# DCSource5V0.net
KiCad netlist of a schematic drawn in Altium Designer
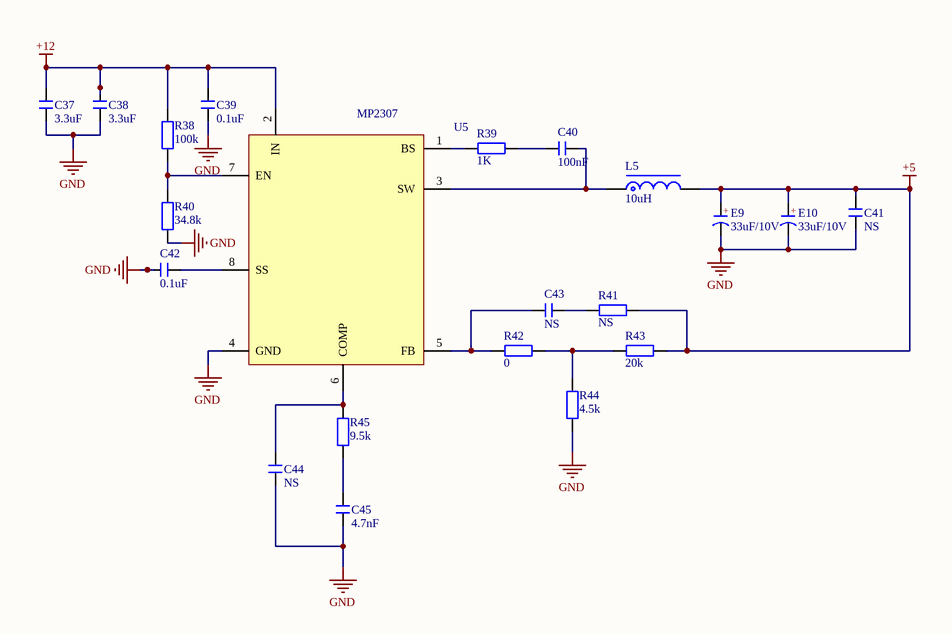
[diagram p0: DCSource5V0.SchDoc]

(export (version "E")
  (design (tool "Eeschema 10.0.6"))
  (components
    (comp (ref "C37")
      (value "3.3uF")
      (footprint "C 0805_L")
      (description "无极性贴片电容")
      (libsource (lib "电容-电阻-电感-电位器") (part "C"))
    )
    (comp (ref "C38")
      (value "3.3uF")
      (footprint "C 0805_L")
      (description "无极性贴片电容")
      (libsource (lib "电容-电阻-电感-电位器") (part "C"))
    )
    (comp (ref "C39")
      (value "0.1uF")
      (footprint "C 0805_L")
      (description "无极性贴片电容")
      (libsource (lib "电容-电阻-电感-电位器") (part "C"))
    )
    (comp (ref "C40")
      (value "100nF")
      (footprint "C 0805_L")
      (description "无极性贴片电容")
      (libsource (lib "电容-电阻-电感-电位器") (part "C"))
    )
    (comp (ref "C41")
      (value "NS")
      (footprint "C 0805_L")
      (description "无极性贴片电容")
      (libsource (lib "电容-电阻-电感-电位器") (part "C"))
    )
    (comp (ref "C42")
      (value "0.1uF")
      (footprint "C 0805_L")
      (description "无极性贴片电容")
      (libsource (lib "电容-电阻-电感-电位器") (part "C"))
    )
    (comp (ref "C43")
      (value "NS")
      (footprint "C 0805_L")
      (description "无极性贴片电容")
      (libsource (lib "电容-电阻-电感-电位器") (part "C"))
    )
    (comp (ref "C44")
      (value "NS")
      (footprint "C 0805_L")
      (description "无极性贴片电容")
      (libsource (lib "电容-电阻-电感-电位器") (part "C"))
    )
    (comp (ref "C45")
      (value "4.7nF")
      (footprint "C 0805_L")
      (description "无极性贴片电容")
      (libsource (lib "电容-电阻-电感-电位器") (part "C"))
    )
    (comp (ref "E9")
      (value "33uF/10V")
      (footprint "CT 5*6 - C")
      (description "贴片固态电容")
      (libsource (lib "电容-电阻-电感-电位器") (part "C-CT"))
    )
    (comp (ref "E10")
      (value "33uF/10V")
      (footprint "CT 5*6 - C")
      (description "贴片固态电容")
      (libsource (lib "电容-电阻-电感-电位器") (part "C-CT"))
    )
    (comp (ref "L5")
      (value "10uH")
      (footprint "CD31")
      (description "贴片功率电感")
      (libsource (lib "电容-电阻-电感-电位器") (part "L-CD"))
    )
    (comp (ref "R38")
      (value "100k")
      (footprint "R 0805_L")
      (description "贴片电阻")
      (libsource (lib "电容-电阻-电感-电位器") (part "R"))
    )
    (comp (ref "R39")
      (value "1K")
      (footprint "R 0805_L")
      (description "贴片电阻")
      (libsource (lib "电容-电阻-电感-电位器") (part "R"))
    )
    (comp (ref "R40")
      (value "34.8k")
      (footprint "R 0805_L")
      (description "贴片电阻")
      (libsource (lib "电容-电阻-电感-电位器") (part "R"))
    )
    (comp (ref "R41")
      (value "NS")
      (footprint "R 0805_L")
      (description "贴片电阻")
      (libsource (lib "电容-电阻-电感-电位器") (part "R"))
    )
    (comp (ref "R42")
      (value "0")
      (footprint "R 0805_L")
      (description "贴片电阻")
      (libsource (lib "电容-电阻-电感-电位器") (part "R"))
    )
    (comp (ref "R43")
      (value "20k")
      (footprint "R 0805_L")
      (description "贴片电阻")
      (libsource (lib "电容-电阻-电感-电位器") (part "R"))
    )
    (comp (ref "R44")
      (value "4.5k")
      (footprint "R 0805_L")
      (description "贴片电阻")
      (libsource (lib "电容-电阻-电感-电位器") (part "R"))
    )
    (comp (ref "R45")
      (value "9.5k")
      (footprint "R 0805_L")
      (description "贴片电阻")
      (libsource (lib "电容-电阻-电感-电位器") (part "R"))
    )
    (comp (ref "U5") (value "MP2307") (footprint "SOP8_M") (libsource (lib "Schlib1") (part "Component_1")))
  )
  (nets
    (net (code "1") (name "+5") (class "Default")
      (node (ref "C41") (pin "2") (pinfunction "2_2") (pintype "passive"))
      (node (ref "E10") (pin "1") (pinfunction "A_1") (pintype "passive"))
      (node (ref "E9") (pin "1") (pinfunction "A_1") (pintype "passive"))
      (node (ref "L5") (pin "2") (pinfunction "2_2") (pintype "passive"))
      (node (ref "R41") (pin "1") (pinfunction "1_1") (pintype "passive"))
      (node (ref "R43") (pin "2") (pinfunction "2_2") (pintype "passive"))
    )
    (net (code "2") (name "+12") (class "Default")
      (node (ref "C37") (pin "2") (pinfunction "2_2") (pintype "passive"))
      (node (ref "C38") (pin "2") (pinfunction "2_2") (pintype "passive"))
      (node (ref "C39") (pin "2") (pinfunction "2_2") (pintype "passive"))
      (node (ref "R38") (pin "2") (pinfunction "2_2") (pintype "passive"))
      (node (ref "U5") (pin "2") (pinfunction "IN_2") (pintype "passive"))
    )
    (net (code "3") (name "GND") (class "Default")
      (node (ref "C37") (pin "1") (pinfunction "1_1") (pintype "passive"))
      (node (ref "C38") (pin "1") (pinfunction "1_1") (pintype "passive"))
      (node (ref "C39") (pin "1") (pinfunction "1_1") (pintype "passive"))
      (node (ref "C41") (pin "1") (pinfunction "1_1") (pintype "passive"))
      (node (ref "C42") (pin "2") (pinfunction "2_2") (pintype "passive"))
      (node (ref "C44") (pin "1") (pinfunction "1_1") (pintype "passive"))
      (node (ref "C45") (pin "1") (pinfunction "1_1") (pintype "passive"))
      (node (ref "E10") (pin "2") (pinfunction "K_2") (pintype "passive"))
      (node (ref "E9") (pin "2") (pinfunction "K_2") (pintype "passive"))
      (node (ref "R40") (pin "1") (pinfunction "1_1") (pintype "passive"))
      (node (ref "R44") (pin "1") (pinfunction "1_1") (pintype "passive"))
      (node (ref "U5") (pin "4") (pinfunction "GND_4") (pintype "passive"))
    )
    (net (code "4") (name "Net-(C40-Pad1)") (class "Default")
      (node (ref "C40") (pin "1") (pinfunction "1_1") (pintype "passive"))
      (node (ref "R39") (pin "2") (pinfunction "2_2") (pintype "passive"))
    )
    (net (code "5") (name "Net-(C43-Pad2)") (class "Default")
      (node (ref "C43") (pin "2") (pinfunction "2_2") (pintype "passive"))
      (node (ref "R41") (pin "2") (pinfunction "2_2") (pintype "passive"))
    )
    (net (code "6") (name "Net-(C45-Pad2)") (class "Default")
      (node (ref "C45") (pin "2") (pinfunction "2_2") (pintype "passive"))
      (node (ref "R45") (pin "1") (pinfunction "1_1") (pintype "passive"))
    )
    (net (code "7") (name "Net-(R42-Pad2)") (class "Default")
      (node (ref "R42") (pin "2") (pinfunction "2_2") (pintype "passive"))
      (node (ref "R43") (pin "1") (pinfunction "1_1") (pintype "passive"))
      (node (ref "R44") (pin "2") (pinfunction "2_2") (pintype "passive"))
    )
    (net (code "8") (name "Net-(U5-BS)") (class "Default")
      (node (ref "R39") (pin "1") (pinfunction "1_1") (pintype "passive"))
      (node (ref "U5") (pin "1") (pinfunction "BS_1") (pintype "passive"))
    )
    (net (code "9") (name "Net-(U5-COMP)") (class "Default")
      (node (ref "C44") (pin "2") (pinfunction "2_2") (pintype "passive"))
      (node (ref "R45") (pin "2") (pinfunction "2_2") (pintype "passive"))
      (node (ref "U5") (pin "6") (pinfunction "COMP_6") (pintype "passive"))
    )
    (net (code "10") (name "Net-(U5-EN)") (class "Default")
      (node (ref "R38") (pin "1") (pinfunction "1_1") (pintype "passive"))
      (node (ref "R40") (pin "2") (pinfunction "2_2") (pintype "passive"))
      (node (ref "U5") (pin "7") (pinfunction "EN_7") (pintype "passive"))
    )
    (net (code "11") (name "Net-(U5-FB)") (class "Default")
      (node (ref "C43") (pin "1") (pinfunction "1_1") (pintype "passive"))
      (node (ref "R42") (pin "1") (pinfunction "1_1") (pintype "passive"))
      (node (ref "U5") (pin "5") (pinfunction "FB_5") (pintype "passive"))
    )
    (net (code "12") (name "Net-(U5-SS)") (class "Default")
      (node (ref "C42") (pin "1") (pinfunction "1_1") (pintype "passive"))
      (node (ref "U5") (pin "8") (pinfunction "SS_8") (pintype "passive"))
    )
    (net (code "13") (name "Net-(U5-SW)") (class "Default")
      (node (ref "C40") (pin "2") (pinfunction "2_2") (pintype "passive"))
      (node (ref "L5") (pin "1") (pinfunction "1_1") (pintype "passive"))
      (node (ref "U5") (pin "3") (pinfunction "SW_3") (pintype "passive"))
    )
  )
)
